# caps-lock-buzzer.net
KiCad netlist of a schematic drawn in EAGLE
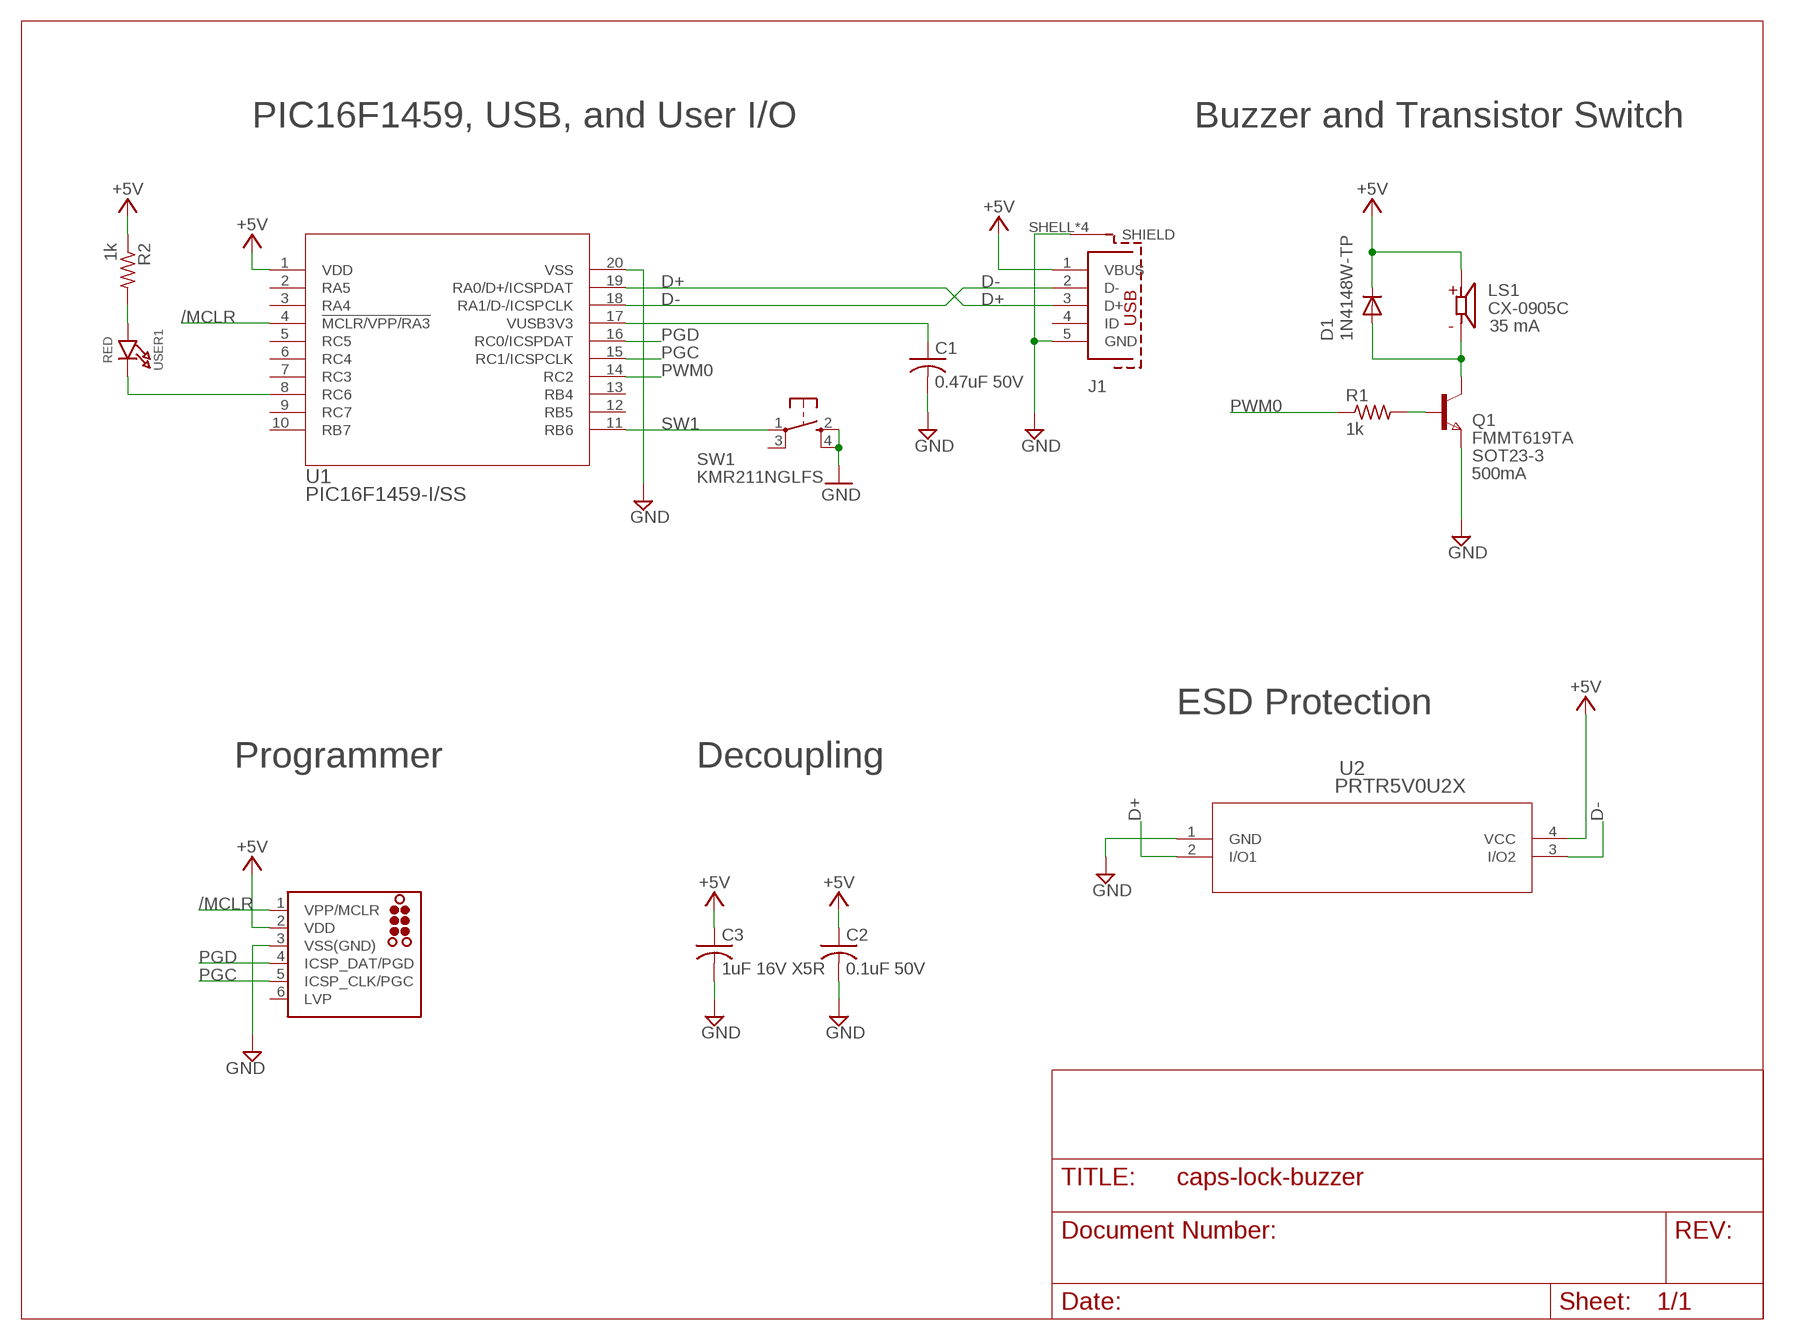
[diagram p0: schematic, sheet 1]

(export (version "E")
  (design (tool "Eeschema 10.0.6"))
  (components
    (comp (ref "C1")
      (value "0.47uF 50V")
      (footprint "eagle-import:C1206K")
      (fields (field (name "MFR") "KEMET") (field (name "MFR_PART_NO") "C1206C474K5RACTU"))
      (libsource (lib "eagle-import") (part "C-USC1206K"))
    )
    (comp (ref "C2")
      (value "0.1uF 50V")
      (footprint "eagle-import:C1206K")
      (fields (field (name "MFR") "KEMET") (field (name "MFR_PART_NO") "C1206S104M5RACTU"))
      (libsource (lib "eagle-import") (part "C-USC1206K"))
    )
    (comp (ref "C3")
      (value "1uF 16V X5R")
      (footprint "eagle-import:C1210")
      (fields (field (name "MFR") "KEMET") (field (name "MFR_PART_NO") "C1210C105K4PACTU"))
      (libsource (lib "eagle-import") (part "C-USC1210"))
    )
    (comp (ref "D1")
      (value "1N4148W-TP")
      (footprint "eagle-import:SOD123")
      (libsource (lib "eagle-import") (part "DIODE-SOD123"))
    )
    (comp (ref "J1")
      (value "629105136821")
      (footprint "eagle-import:629105136821")
      (libsource (lib "eagle-import") (part "629105136821"))
    )
    (comp (ref "J3")
      (value "TC2030-MCP-NL")
      (footprint "eagle-import:TC2030-MCP-NL")
      (libsource (lib "eagle-import") (part "TC2030-MCP-NL"))
    )
    (comp (ref "LS1")
      (value "CX-0905C")
      (footprint "eagle-import:CUI_CX-0905C")
      (fields (field (name "MF") "CUI"))
      (libsource (lib "eagle-import") (part "CX-0905C"))
    )
    (comp (ref "Q1")
      (value "FMMT619TA")
      (footprint "eagle-import:SOT-23")
      (fields (field (name "MPN") "DSS20201L-7"))
      (libsource (lib "eagle-import") (part "NPNSOT23"))
    )
    (comp (ref "R1")
      (value "1k")
      (footprint "eagle-import:R0805")
      (libsource (lib "eagle-import") (part "R-US_R0805"))
    )
    (comp (ref "R2")
      (value "1k")
      (footprint "eagle-import:R0805")
      (libsource (lib "eagle-import") (part "R-US_R0805"))
    )
    (comp (ref "SW1")
      (value "KMR211NGLFS")
      (footprint "eagle-import:KMR2")
      (libsource (lib "eagle-import") (part "SPST_TACT-KMR2"))
    )
    (comp (ref "U1")
      (value "PIC16F1459-I/SS")
      (footprint "eagle-import:SSOP20_MC")
      (fields (field (name "MANUFACTURER_PART_NUMBER") "PIC16F1459ISS"))
      (libsource (lib "eagle-import") (part "PIC16F1459-I/SS"))
    )
    (comp (ref "U2")
      (value "PRTR5V0U2X")
      (footprint "eagle-import:SOT143B")
      (libsource (lib "eagle-import") (part "PRTR5V0U2X"))
    )
    (comp (ref "USER1")
      (value "RED")
      (footprint "eagle-import:CHIPLED_0805_NOOUTLINE")
      (libsource (lib "eagle-import") (part "LED0805_NOOUTLINE"))
    )
  )
  (nets
    (net (code "1") (name "+5V") (class "Default")
      (node (ref "C2") (pin "1") (pinfunction "1_1") (pintype "passive"))
      (node (ref "C3") (pin "1") (pinfunction "1_1") (pintype "passive"))
      (node (ref "D1") (pin "C") (pinfunction "C_C") (pintype "passive"))
      (node (ref "J1") (pin "1") (pinfunction "VBUS_1") (pintype "passive"))
      (node (ref "J3") (pin "2") (pinfunction "VDD_2") (pintype "power_in"))
      (node (ref "LS1") (pin "P") (pinfunction "P_P") (pintype "passive"))
      (node (ref "R2") (pin "1") (pinfunction "1_1") (pintype "passive"))
      (node (ref "U1") (pin "1") (pinfunction "VDD_1") (pintype "power_in"))
      (node (ref "U2") (pin "4") (pinfunction "VCC_4") (pintype "passive"))
    )
    (net (code "2") (name "/D+") (class "Default")
      (node (ref "J1") (pin "3") (pinfunction "D+_3") (pintype "passive"))
      (node (ref "U1") (pin "19") (pinfunction "RA0/D+/ICSPDAT_19") (pintype "bidirectional"))
      (node (ref "U2") (pin "2") (pinfunction "I/O1_2") (pintype "passive"))
    )
    (net (code "3") (name "/D-") (class "Default")
      (node (ref "J1") (pin "2") (pinfunction "D-_2") (pintype "passive"))
      (node (ref "U1") (pin "18") (pinfunction "RA1/D-/ICSPCLK_18") (pintype "bidirectional"))
      (node (ref "U2") (pin "3") (pinfunction "I/O2_3") (pintype "passive"))
    )
    (net (code "4") (name "/PGC") (class "Default")
      (node (ref "J3") (pin "5") (pinfunction "ICSP_CLK/PGC_5") (pintype "output"))
      (node (ref "U1") (pin "15") (pinfunction "RC1/ICSPCLK_15") (pintype "bidirectional"))
    )
    (net (code "5") (name "/PGD") (class "Default")
      (node (ref "J3") (pin "4") (pinfunction "ICSP_DAT/PGD_4") (pintype "bidirectional"))
      (node (ref "U1") (pin "16") (pinfunction "RC0/ICSPDAT_16") (pintype "bidirectional"))
    )
    (net (code "6") (name "/PWM0") (class "Default")
      (node (ref "R1") (pin "1") (pinfunction "1_1") (pintype "passive"))
      (node (ref "U1") (pin "14") (pinfunction "RC2_14") (pintype "bidirectional"))
    )
    (net (code "7") (name "/SW1") (class "Default")
      (node (ref "SW1") (pin "1") (pinfunction "P_1") (pintype "passive"))
      (node (ref "U1") (pin "11") (pinfunction "RB6_11") (pintype "bidirectional"))
    )
    (net (code "8") (name "/{slash}MCLR") (class "Default")
      (node (ref "J3") (pin "1") (pinfunction "VPP/MCLR_1") (pintype "passive"))
      (node (ref "U1") (pin "4") (pinfunction "~{MCLR/VPP/RA3}_4") (pintype "bidirectional"))
    )
    (net (code "9") (name "GND") (class "Default")
      (node (ref "C1") (pin "2") (pinfunction "2_2") (pintype "passive"))
      (node (ref "C2") (pin "2") (pinfunction "2_2") (pintype "passive"))
      (node (ref "C3") (pin "2") (pinfunction "2_2") (pintype "passive"))
      (node (ref "J1") (pin "5") (pinfunction "GND_5") (pintype "passive"))
      (node (ref "J1") (pin "SHELL") (pinfunction "SHIELD_SHELL") (pintype "passive"))
      (node (ref "J1") (pin "SHELL1") (pinfunction "SHIELD_SHELL1") (pintype "passive"))
      (node (ref "J1") (pin "SHELL2") (pinfunction "SHIELD_SHELL2") (pintype "passive"))
      (node (ref "J1") (pin "SHELL3") (pinfunction "SHIELD_SHELL3") (pintype "passive"))
      (node (ref "J3") (pin "3") (pinfunction "VSS(GND)_3") (pintype "power_in"))
      (node (ref "Q1") (pin "2") (pinfunction "E_2") (pintype "passive"))
      (node (ref "SW1") (pin "2") (pinfunction "S_2") (pintype "passive"))
      (node (ref "SW1") (pin "4") (pinfunction "S1_4") (pintype "passive"))
      (node (ref "U1") (pin "20") (pinfunction "VSS_20") (pintype "power_in"))
      (node (ref "U2") (pin "1") (pinfunction "GND_1") (pintype "passive"))
    )
    (net (code "10") (name "Net-(Q1-B)") (class "Default")
      (node (ref "Q1") (pin "3") (pinfunction "B_3") (pintype "passive"))
      (node (ref "R1") (pin "2") (pinfunction "2_2") (pintype "passive"))
    )
    (net (code "11") (name "Net-(Q1-C)") (class "Default")
      (node (ref "D1") (pin "A") (pinfunction "A_A") (pintype "passive"))
      (node (ref "LS1") (pin "N") (pinfunction "N_N") (pintype "passive"))
      (node (ref "Q1") (pin "1") (pinfunction "C_1") (pintype "passive"))
    )
    (net (code "12") (name "Net-(R2-Pad2)") (class "Default")
      (node (ref "R2") (pin "2") (pinfunction "2_2") (pintype "passive"))
      (node (ref "USER1") (pin "A") (pinfunction "A_A") (pintype "passive"))
    )
    (net (code "13") (name "Net-(U1-RC6)") (class "Default")
      (node (ref "U1") (pin "8") (pinfunction "RC6_8") (pintype "bidirectional"))
      (node (ref "USER1") (pin "C") (pinfunction "C_C") (pintype "passive"))
    )
    (net (code "14") (name "Net-(U1-VUSB3V3)") (class "Default")
      (node (ref "C1") (pin "1") (pinfunction "1_1") (pintype "passive"))
      (node (ref "U1") (pin "17") (pinfunction "VUSB3V3_17") (pintype "power_in"))
    )
    (net (code "15") (name "unconnected-(J1-ID-Pad4)") (class "Default")
      (node (ref "J1") (pin "4") (pinfunction "ID_4") (pintype "passive"))
    )
    (net (code "16") (name "unconnected-(J3-LVP-Pad6)") (class "Default")
      (node (ref "J3") (pin "6") (pinfunction "LVP_6") (pintype "bidirectional"))
    )
    (net (code "17") (name "unconnected-(SW1-P1-Pad3)") (class "Default")
      (node (ref "SW1") (pin "3") (pinfunction "P1_3") (pintype "passive"))
    )
    (net (code "18") (name "unconnected-(U1-RA4-Pad3)") (class "Default")
      (node (ref "U1") (pin "3") (pinfunction "RA4_3") (pintype "bidirectional"))
    )
    (net (code "19") (name "unconnected-(U1-RA5-Pad2)") (class "Default")
      (node (ref "U1") (pin "2") (pinfunction "RA5_2") (pintype "bidirectional"))
    )
    (net (code "20") (name "unconnected-(U1-RB4-Pad13)") (class "Default")
      (node (ref "U1") (pin "13") (pinfunction "RB4_13") (pintype "bidirectional"))
    )
    (net (code "21") (name "unconnected-(U1-RB5-Pad12)") (class "Default")
      (node (ref "U1") (pin "12") (pinfunction "RB5_12") (pintype "bidirectional"))
    )
    (net (code "22") (name "unconnected-(U1-RB7-Pad10)") (class "Default")
      (node (ref "U1") (pin "10") (pinfunction "RB7_10") (pintype "bidirectional"))
    )
    (net (code "23") (name "unconnected-(U1-RC3-Pad7)") (class "Default")
      (node (ref "U1") (pin "7") (pinfunction "RC3_7") (pintype "bidirectional"))
    )
    (net (code "24") (name "unconnected-(U1-RC4-Pad6)") (class "Default")
      (node (ref "U1") (pin "6") (pinfunction "RC4_6") (pintype "bidirectional"))
    )
    (net (code "25") (name "unconnected-(U1-RC5-Pad5)") (class "Default")
      (node (ref "U1") (pin "5") (pinfunction "RC5_5") (pintype "bidirectional"))
    )
    (net (code "26") (name "unconnected-(U1-RC7-Pad9)") (class "Default")
      (node (ref "U1") (pin "9") (pinfunction "RC7_9") (pintype "bidirectional"))
    )
  )
)
